# IR-Demodulator-Transceiver-v1c.net
KiCad netlist of a schematic drawn in EAGLE
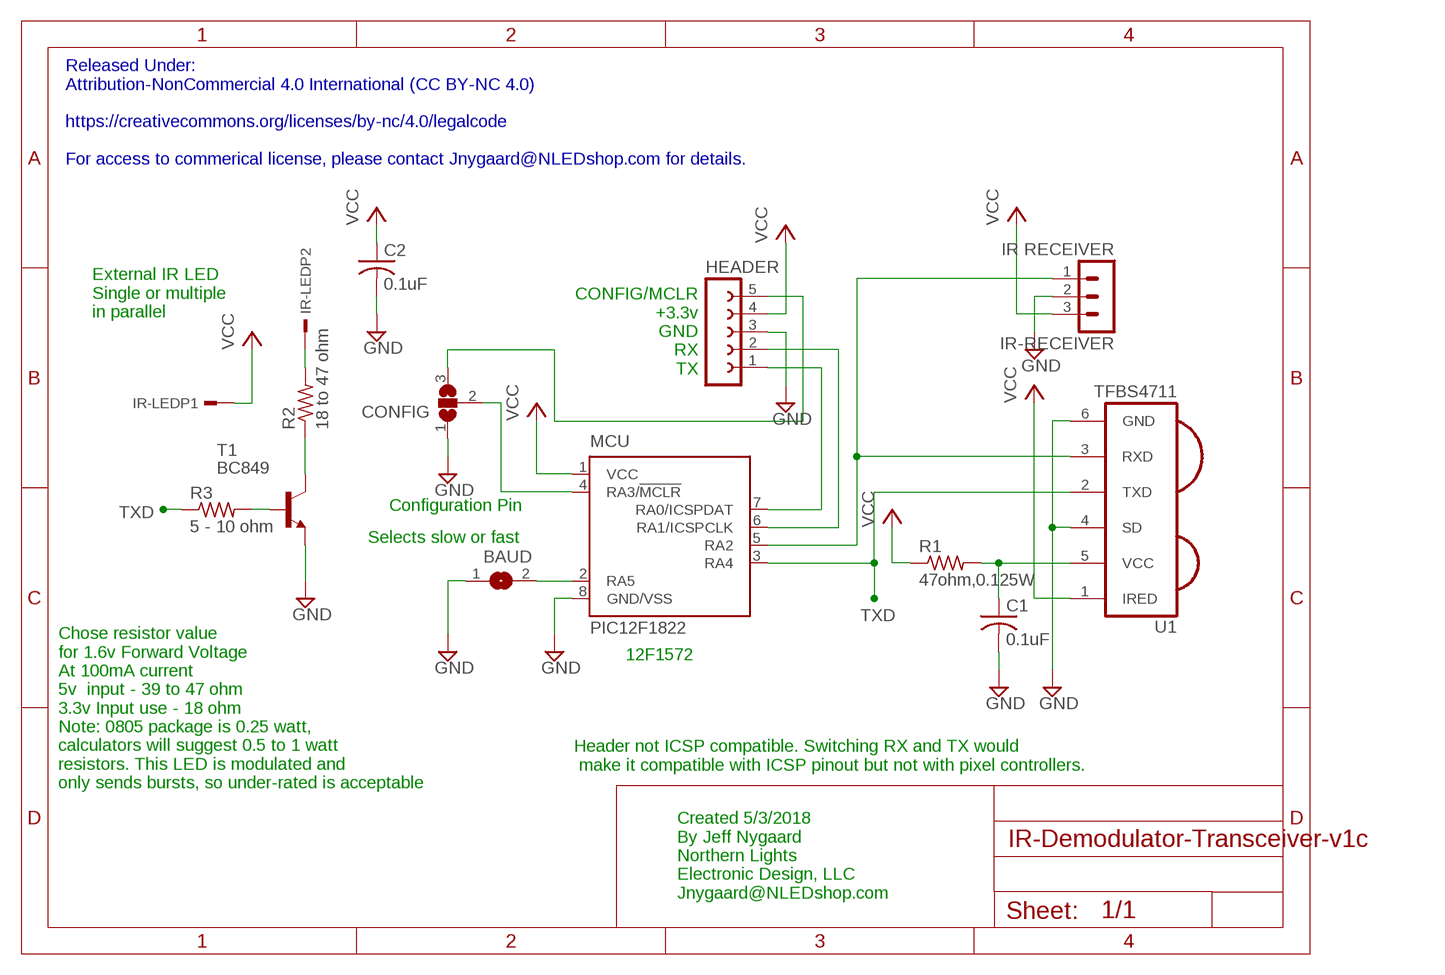
[diagram p0: schematic, sheet 1]

(export (version "E")
  (design (tool "Eeschema 10.0.6"))
  (components
    (comp (ref "BAUD")
      (value "SJ")
      (footprint "eagle-import:SJ")
      (libsource (lib "eagle-import") (part "SJ"))
    )
    (comp (ref "C1")
      (value "0.1uF")
      (footprint "eagle-import:C0805")
      (libsource (lib "eagle-import") (part "C-USC0805"))
    )
    (comp (ref "C2")
      (value "0.1uF")
      (footprint "eagle-import:C0805")
      (libsource (lib "eagle-import") (part "C-USC0805"))
    )
    (comp (ref "CONFIG")
      (value "SJ2W")
      (footprint "eagle-import:SJ_2")
      (libsource (lib "eagle-import") (part "SJ2W"))
    )
    (comp (ref "HEADER")
      (value "FE05-1")
      (footprint "eagle-import:FE05-1")
      (libsource (lib "eagle-import") (part "FE05-1"))
    )
    (comp (ref "IR-LED")
      (value "HEADER-2X1")
      (footprint "eagle-import:HEADER-2X1")
      (libsource (lib "eagle-import") (part "HEADER-2X1"))
    )
    (comp (ref "IR-RECEIVER")
      (value "IR RECEIVER")
      (footprint "eagle-import:MA03-1")
      (libsource (lib "eagle-import") (part "MA03-11"))
    )
    (comp (ref "MCU")
      (value "PIC12F1822")
      (footprint "eagle-import:SOIC-8")
      (libsource (lib "eagle-import") (part "PIC12F1822"))
    )
    (comp (ref "R1")
      (value "47ohm,0.125W")
      (footprint "eagle-import:R0805")
      (libsource (lib "eagle-import") (part "R-US_R0805"))
    )
    (comp (ref "R2")
      (value "18 to 47 ohm")
      (footprint "eagle-import:R0805")
      (libsource (lib "eagle-import") (part "R-US_R0805"))
    )
    (comp (ref "R3")
      (value "5 - 10 ohm")
      (footprint "eagle-import:R0603")
      (libsource (lib "eagle-import") (part "R-US_R0603"))
    )
    (comp (ref "T1")
      (value "BC849")
      (footprint "eagle-import:SOT23")
      (libsource (lib "eagle-import") (part "BC849"))
    )
    (comp (ref "U1")
      (value "TFBS4711")
      (footprint "eagle-import:TFBS4711")
      (libsource (lib "eagle-import") (part "TFBS4711"))
    )
  )
  (nets
    (net (code "1") (name "/TXD") (class "Default")
      (node (ref "MCU") (pin "3") (pinfunction "RA4_3") (pintype "bidirectional"))
      (node (ref "R3") (pin "1") (pinfunction "1_1") (pintype "passive"))
      (node (ref "U1") (pin "2") (pinfunction "TXD_2") (pintype "input"))
    )
    (net (code "2") (name "GND") (class "Default")
      (node (ref "BAUD") (pin "1") (pinfunction "1_1") (pintype "passive"))
      (node (ref "C1") (pin "2") (pinfunction "2_2") (pintype "passive"))
      (node (ref "C2") (pin "2") (pinfunction "2_2") (pintype "passive"))
      (node (ref "CONFIG") (pin "1") (pinfunction "1_1") (pintype "passive"))
      (node (ref "HEADER") (pin "3") (pinfunction "3_3") (pintype "passive"))
      (node (ref "IR-RECEIVER") (pin "2") (pinfunction "2_2") (pintype "passive"))
      (node (ref "MCU") (pin "8") (pinfunction "GND/VSS_8") (pintype "power_in"))
      (node (ref "T1") (pin "2") (pinfunction "E_2") (pintype "passive"))
      (node (ref "U1") (pin "4") (pinfunction "SD_4") (pintype "input"))
      (node (ref "U1") (pin "6") (pinfunction "GND_6") (pintype "power_in"))
    )
    (net (code "3") (name "Net-(CONFIG-Pad3)") (class "Default")
      (node (ref "CONFIG") (pin "3") (pinfunction "3_3") (pintype "passive"))
      (node (ref "HEADER") (pin "5") (pinfunction "5_5") (pintype "passive"))
    )
    (net (code "4") (name "Net-(IR-LEDB-1)") (class "Default")
      (node (ref "IR-LED") (pin "2") (pinfunction "1_2") (pintype "passive"))
      (node (ref "R2") (pin "2") (pinfunction "2_2") (pintype "passive"))
    )
    (net (code "5") (name "Net-(MCU-RA0{slash}ICSPDAT)") (class "Default")
      (node (ref "HEADER") (pin "1") (pinfunction "1_1") (pintype "passive"))
      (node (ref "MCU") (pin "7") (pinfunction "RA0/ICSPDAT_7") (pintype "bidirectional"))
    )
    (net (code "6") (name "Net-(MCU-RA1{slash}ICSPCLK)") (class "Default")
      (node (ref "HEADER") (pin "2") (pinfunction "2_2") (pintype "passive"))
      (node (ref "MCU") (pin "6") (pinfunction "RA1/ICSPCLK_6") (pintype "bidirectional"))
    )
    (net (code "7") (name "Net-(MCU-RA2)") (class "Default")
      (node (ref "IR-RECEIVER") (pin "1") (pinfunction "1_1") (pintype "passive"))
      (node (ref "MCU") (pin "5") (pinfunction "RA2_5") (pintype "bidirectional"))
      (node (ref "U1") (pin "3") (pinfunction "RXD_3") (pintype "output"))
    )
    (net (code "8") (name "Net-(MCU-RA3{slash}~{MCLR})") (class "Default")
      (node (ref "CONFIG") (pin "2") (pinfunction "2_2") (pintype "passive"))
      (node (ref "MCU") (pin "4") (pinfunction "RA3/~{MCLR}_4") (pintype "input"))
    )
    (net (code "9") (name "Net-(MCU-RA5)") (class "Default")
      (node (ref "BAUD") (pin "2") (pinfunction "2_2") (pintype "passive"))
      (node (ref "MCU") (pin "2") (pinfunction "RA5_2") (pintype "bidirectional"))
    )
    (net (code "10") (name "Net-(T1-B)") (class "Default")
      (node (ref "R3") (pin "2") (pinfunction "2_2") (pintype "passive"))
      (node (ref "T1") (pin "1") (pinfunction "B_1") (pintype "passive"))
    )
    (net (code "11") (name "Net-(T1-C)") (class "Default")
      (node (ref "R2") (pin "1") (pinfunction "1_1") (pintype "passive"))
      (node (ref "T1") (pin "3") (pinfunction "C_3") (pintype "passive"))
    )
    (net (code "12") (name "Net-(U1-VCC)") (class "Default")
      (node (ref "C1") (pin "1") (pinfunction "1_1") (pintype "passive"))
      (node (ref "R1") (pin "2") (pinfunction "2_2") (pintype "passive"))
      (node (ref "U1") (pin "5") (pinfunction "VCC_5") (pintype "power_in"))
    )
    (net (code "13") (name "VCC") (class "Default")
      (node (ref "C2") (pin "1") (pinfunction "1_1") (pintype "passive"))
      (node (ref "HEADER") (pin "4") (pinfunction "4_4") (pintype "passive"))
      (node (ref "IR-LED") (pin "1") (pinfunction "1_1") (pintype "passive"))
      (node (ref "IR-RECEIVER") (pin "3") (pinfunction "3_3") (pintype "passive"))
      (node (ref "MCU") (pin "1") (pinfunction "VCC_1") (pintype "power_in"))
      (node (ref "R1") (pin "1") (pinfunction "1_1") (pintype "passive"))
      (node (ref "U1") (pin "1") (pinfunction "IRED_1") (pintype "power_in"))
    )
  )
)
